# backplane.net
KiCad netlist of a schematic drawn in EAGLE
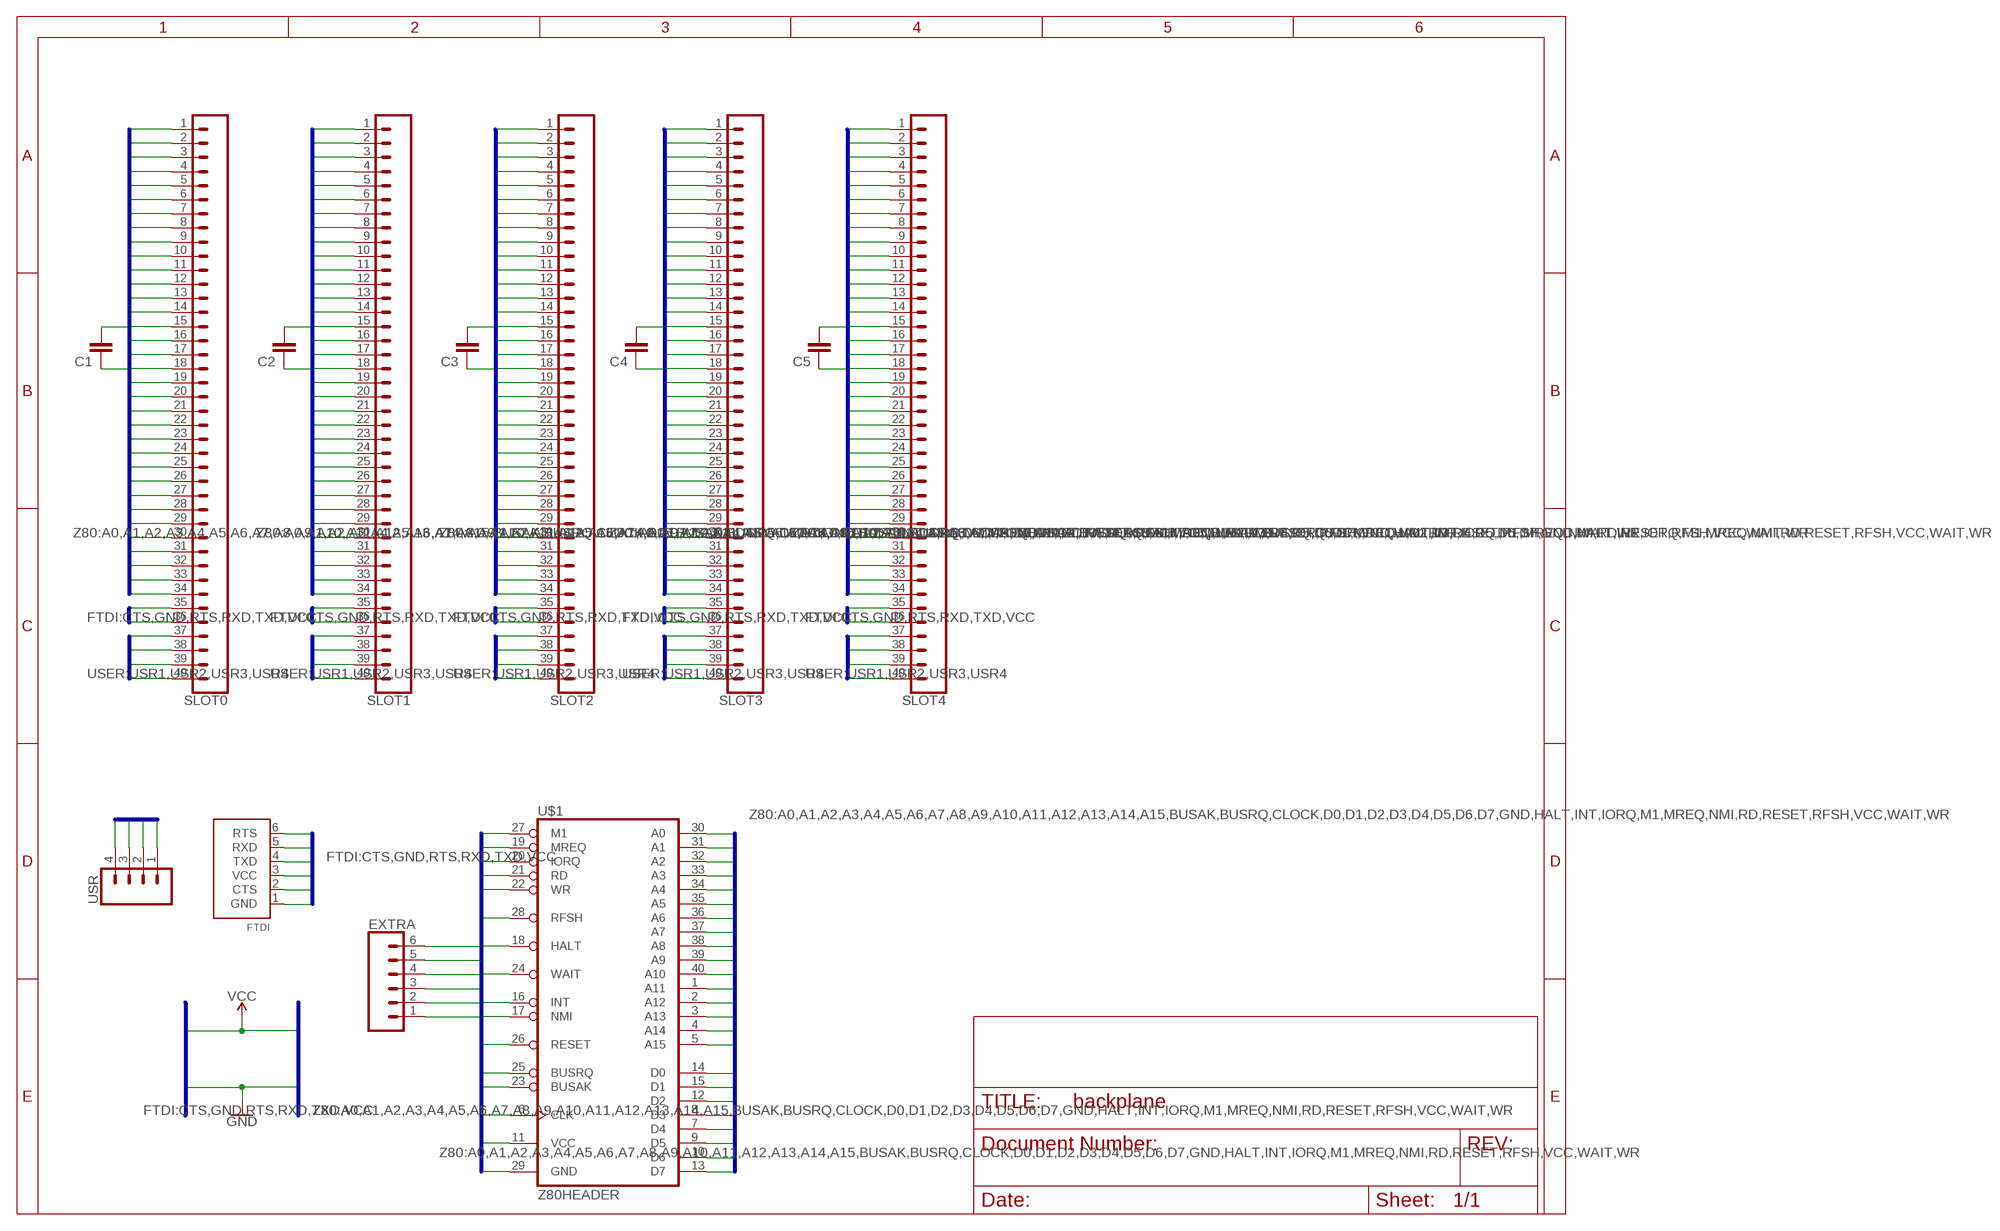
[diagram p0: schematic, sheet 1]

(export (version "E")
  (design (tool "Eeschema 10.0.6"))
  (components
    (comp (ref "C1")
      (value "C2,5-3")
      (footprint "eagle-import:C2.5-3")
      (libsource (lib "eagle-import") (part "C2,5-3"))
    )
    (comp (ref "C2")
      (value "C2,5-3")
      (footprint "eagle-import:C2.5-3")
      (libsource (lib "eagle-import") (part "C2,5-3"))
    )
    (comp (ref "C3")
      (value "C2,5-3")
      (footprint "eagle-import:C2.5-3")
      (libsource (lib "eagle-import") (part "C2,5-3"))
    )
    (comp (ref "C4")
      (value "C2,5-3")
      (footprint "eagle-import:C2.5-3")
      (libsource (lib "eagle-import") (part "C2,5-3"))
    )
    (comp (ref "C5")
      (value "C2,5-3")
      (footprint "eagle-import:C2.5-3")
      (libsource (lib "eagle-import") (part "C2,5-3"))
    )
    (comp (ref "EXTRA")
      (value "CONN_06LOCK")
      (footprint "eagle-import:1X06_LOCK")
      (libsource (lib "eagle-import") (part "CONN_06LOCK"))
    )
    (comp (ref "FTDI")
      (value "FTDIUSBCABLE")
      (footprint "eagle-import:1X06_ROUND")
      (libsource (lib "eagle-import") (part "FTDIUSBCABLE"))
    )
    (comp (ref "SLOT0")
      (value "CONN_40")
      (footprint "eagle-import:1X40")
      (libsource (lib "eagle-import") (part "CONN_40"))
    )
    (comp (ref "SLOT1")
      (value "CONN_40")
      (footprint "eagle-import:1X40")
      (libsource (lib "eagle-import") (part "CONN_40"))
    )
    (comp (ref "SLOT2")
      (value "CONN_40")
      (footprint "eagle-import:1X40")
      (libsource (lib "eagle-import") (part "CONN_40"))
    )
    (comp (ref "SLOT3")
      (value "CONN_40")
      (footprint "eagle-import:1X40")
      (libsource (lib "eagle-import") (part "CONN_40"))
    )
    (comp (ref "SLOT4")
      (value "CONN_40")
      (footprint "eagle-import:1X40")
      (libsource (lib "eagle-import") (part "CONN_40"))
    )
    (comp (ref "U$1")
      (value "Z80HEADER")
      (footprint "eagle-import:2X20")
      (libsource (lib "eagle-import") (part "Z80HEADER"))
    )
    (comp (ref "USR")
      (value "CONN_04PTH")
      (footprint "eagle-import:1X04")
      (libsource (lib "eagle-import") (part "CONN_04PTH"))
    )
  )
  (nets
    (net (code "4") (name "/A0") (class "Default")
      (node (ref "SLOT0") (pin "16") (pinfunction "16_16") (pintype "passive"))
      (node (ref "SLOT1") (pin "16") (pinfunction "16_16") (pintype "passive"))
      (node (ref "SLOT2") (pin "16") (pinfunction "16_16") (pintype "passive"))
      (node (ref "SLOT3") (pin "16") (pinfunction "16_16") (pintype "passive"))
      (node (ref "SLOT4") (pin "16") (pinfunction "16_16") (pintype "passive"))
      (node (ref "U$1") (pin "30") (pinfunction "A0_30") (pintype "output"))
    )
    (net (code "5") (name "/A1") (class "Default")
      (node (ref "SLOT0") (pin "15") (pinfunction "15_15") (pintype "passive"))
      (node (ref "SLOT1") (pin "15") (pinfunction "15_15") (pintype "passive"))
      (node (ref "SLOT2") (pin "15") (pinfunction "15_15") (pintype "passive"))
      (node (ref "SLOT3") (pin "15") (pinfunction "15_15") (pintype "passive"))
      (node (ref "SLOT4") (pin "15") (pinfunction "15_15") (pintype "passive"))
      (node (ref "U$1") (pin "31") (pinfunction "A1_31") (pintype "output"))
    )
    (net (code "6") (name "/A2") (class "Default")
      (node (ref "SLOT0") (pin "14") (pinfunction "14_14") (pintype "passive"))
      (node (ref "SLOT1") (pin "14") (pinfunction "14_14") (pintype "passive"))
      (node (ref "SLOT2") (pin "14") (pinfunction "14_14") (pintype "passive"))
      (node (ref "SLOT3") (pin "14") (pinfunction "14_14") (pintype "passive"))
      (node (ref "SLOT4") (pin "14") (pinfunction "14_14") (pintype "passive"))
      (node (ref "U$1") (pin "32") (pinfunction "A2_32") (pintype "output"))
    )
    (net (code "7") (name "/A3") (class "Default")
      (node (ref "SLOT0") (pin "13") (pinfunction "13_13") (pintype "passive"))
      (node (ref "SLOT1") (pin "13") (pinfunction "13_13") (pintype "passive"))
      (node (ref "SLOT2") (pin "13") (pinfunction "13_13") (pintype "passive"))
      (node (ref "SLOT3") (pin "13") (pinfunction "13_13") (pintype "passive"))
      (node (ref "SLOT4") (pin "13") (pinfunction "13_13") (pintype "passive"))
      (node (ref "U$1") (pin "33") (pinfunction "A3_33") (pintype "output"))
    )
    (net (code "8") (name "/A4") (class "Default")
      (node (ref "SLOT0") (pin "12") (pinfunction "12_12") (pintype "passive"))
      (node (ref "SLOT1") (pin "12") (pinfunction "12_12") (pintype "passive"))
      (node (ref "SLOT2") (pin "12") (pinfunction "12_12") (pintype "passive"))
      (node (ref "SLOT3") (pin "12") (pinfunction "12_12") (pintype "passive"))
      (node (ref "SLOT4") (pin "12") (pinfunction "12_12") (pintype "passive"))
      (node (ref "U$1") (pin "34") (pinfunction "A4_34") (pintype "output"))
    )
    (net (code "9") (name "/A5") (class "Default")
      (node (ref "SLOT0") (pin "11") (pinfunction "11_11") (pintype "passive"))
      (node (ref "SLOT1") (pin "11") (pinfunction "11_11") (pintype "passive"))
      (node (ref "SLOT2") (pin "11") (pinfunction "11_11") (pintype "passive"))
      (node (ref "SLOT3") (pin "11") (pinfunction "11_11") (pintype "passive"))
      (node (ref "SLOT4") (pin "11") (pinfunction "11_11") (pintype "passive"))
      (node (ref "U$1") (pin "35") (pinfunction "A5_35") (pintype "output"))
    )
    (net (code "10") (name "/A6") (class "Default")
      (node (ref "SLOT0") (pin "10") (pinfunction "10_10") (pintype "passive"))
      (node (ref "SLOT1") (pin "10") (pinfunction "10_10") (pintype "passive"))
      (node (ref "SLOT2") (pin "10") (pinfunction "10_10") (pintype "passive"))
      (node (ref "SLOT3") (pin "10") (pinfunction "10_10") (pintype "passive"))
      (node (ref "SLOT4") (pin "10") (pinfunction "10_10") (pintype "passive"))
      (node (ref "U$1") (pin "36") (pinfunction "A6_36") (pintype "output"))
    )
    (net (code "11") (name "/A7") (class "Default")
      (node (ref "SLOT0") (pin "9") (pinfunction "9_9") (pintype "passive"))
      (node (ref "SLOT1") (pin "9") (pinfunction "9_9") (pintype "passive"))
      (node (ref "SLOT2") (pin "9") (pinfunction "9_9") (pintype "passive"))
      (node (ref "SLOT3") (pin "9") (pinfunction "9_9") (pintype "passive"))
      (node (ref "SLOT4") (pin "9") (pinfunction "9_9") (pintype "passive"))
      (node (ref "U$1") (pin "37") (pinfunction "A7_37") (pintype "output"))
    )
    (net (code "12") (name "/A8") (class "Default")
      (node (ref "SLOT0") (pin "8") (pinfunction "8_8") (pintype "passive"))
      (node (ref "SLOT1") (pin "8") (pinfunction "8_8") (pintype "passive"))
      (node (ref "SLOT2") (pin "8") (pinfunction "8_8") (pintype "passive"))
      (node (ref "SLOT3") (pin "8") (pinfunction "8_8") (pintype "passive"))
      (node (ref "SLOT4") (pin "8") (pinfunction "8_8") (pintype "passive"))
      (node (ref "U$1") (pin "38") (pinfunction "A8_38") (pintype "output"))
    )
    (net (code "13") (name "/A9") (class "Default")
      (node (ref "SLOT0") (pin "7") (pinfunction "7_7") (pintype "passive"))
      (node (ref "SLOT1") (pin "7") (pinfunction "7_7") (pintype "passive"))
      (node (ref "SLOT2") (pin "7") (pinfunction "7_7") (pintype "passive"))
      (node (ref "SLOT3") (pin "7") (pinfunction "7_7") (pintype "passive"))
      (node (ref "SLOT4") (pin "7") (pinfunction "7_7") (pintype "passive"))
      (node (ref "U$1") (pin "39") (pinfunction "A9_39") (pintype "output"))
    )
    (net (code "14") (name "/A10") (class "Default")
      (node (ref "SLOT0") (pin "6") (pinfunction "6_6") (pintype "passive"))
      (node (ref "SLOT1") (pin "6") (pinfunction "6_6") (pintype "passive"))
      (node (ref "SLOT2") (pin "6") (pinfunction "6_6") (pintype "passive"))
      (node (ref "SLOT3") (pin "6") (pinfunction "6_6") (pintype "passive"))
      (node (ref "SLOT4") (pin "6") (pinfunction "6_6") (pintype "passive"))
      (node (ref "U$1") (pin "40") (pinfunction "A10_40") (pintype "output"))
    )
    (net (code "15") (name "/A11") (class "Default")
      (node (ref "SLOT0") (pin "5") (pinfunction "5_5") (pintype "passive"))
      (node (ref "SLOT1") (pin "5") (pinfunction "5_5") (pintype "passive"))
      (node (ref "SLOT2") (pin "5") (pinfunction "5_5") (pintype "passive"))
      (node (ref "SLOT3") (pin "5") (pinfunction "5_5") (pintype "passive"))
      (node (ref "SLOT4") (pin "5") (pinfunction "5_5") (pintype "passive"))
      (node (ref "U$1") (pin "1") (pinfunction "A11_1") (pintype "output"))
    )
    (net (code "16") (name "/A12") (class "Default")
      (node (ref "SLOT0") (pin "4") (pinfunction "4_4") (pintype "passive"))
      (node (ref "SLOT1") (pin "4") (pinfunction "4_4") (pintype "passive"))
      (node (ref "SLOT2") (pin "4") (pinfunction "4_4") (pintype "passive"))
      (node (ref "SLOT3") (pin "4") (pinfunction "4_4") (pintype "passive"))
      (node (ref "SLOT4") (pin "4") (pinfunction "4_4") (pintype "passive"))
      (node (ref "U$1") (pin "2") (pinfunction "A12_2") (pintype "output"))
    )
    (net (code "17") (name "/A13") (class "Default")
      (node (ref "SLOT0") (pin "3") (pinfunction "3_3") (pintype "passive"))
      (node (ref "SLOT1") (pin "3") (pinfunction "3_3") (pintype "passive"))
      (node (ref "SLOT2") (pin "3") (pinfunction "3_3") (pintype "passive"))
      (node (ref "SLOT3") (pin "3") (pinfunction "3_3") (pintype "passive"))
      (node (ref "SLOT4") (pin "3") (pinfunction "3_3") (pintype "passive"))
      (node (ref "U$1") (pin "3") (pinfunction "A13_3") (pintype "output"))
    )
    (net (code "18") (name "/A14") (class "Default")
      (node (ref "SLOT0") (pin "2") (pinfunction "2_2") (pintype "passive"))
      (node (ref "SLOT1") (pin "2") (pinfunction "2_2") (pintype "passive"))
      (node (ref "SLOT2") (pin "2") (pinfunction "2_2") (pintype "passive"))
      (node (ref "SLOT3") (pin "2") (pinfunction "2_2") (pintype "passive"))
      (node (ref "SLOT4") (pin "2") (pinfunction "2_2") (pintype "passive"))
      (node (ref "U$1") (pin "4") (pinfunction "A14_4") (pintype "output"))
    )
    (net (code "19") (name "/A15") (class "Default")
      (node (ref "SLOT0") (pin "1") (pinfunction "1_1") (pintype "passive"))
      (node (ref "SLOT1") (pin "1") (pinfunction "1_1") (pintype "passive"))
      (node (ref "SLOT2") (pin "1") (pinfunction "1_1") (pintype "passive"))
      (node (ref "SLOT3") (pin "1") (pinfunction "1_1") (pintype "passive"))
      (node (ref "SLOT4") (pin "1") (pinfunction "1_1") (pintype "passive"))
      (node (ref "U$1") (pin "5") (pinfunction "A15_5") (pintype "output"))
    )
    (net (code "20") (name "/BUSAK") (class "Default")
      (node (ref "EXTRA") (pin "6") (pinfunction "6_6") (pintype "passive"))
      (node (ref "U$1") (pin "23") (pinfunction "BUSAK_23") (pintype "output"))
    )
    (net (code "21") (name "/BUSRQ") (class "Default")
      (node (ref "EXTRA") (pin "5") (pinfunction "5_5") (pintype "passive"))
      (node (ref "U$1") (pin "25") (pinfunction "BUSRQ_25") (pintype "input"))
    )
    (net (code "22") (name "/CLOCK") (class "Default")
      (node (ref "SLOT0") (pin "21") (pinfunction "21_21") (pintype "passive"))
      (node (ref "SLOT1") (pin "21") (pinfunction "21_21") (pintype "passive"))
      (node (ref "SLOT2") (pin "21") (pinfunction "21_21") (pintype "passive"))
      (node (ref "SLOT3") (pin "21") (pinfunction "21_21") (pintype "passive"))
      (node (ref "SLOT4") (pin "21") (pinfunction "21_21") (pintype "passive"))
      (node (ref "U$1") (pin "6") (pinfunction "CLK_6") (pintype "input"))
    )
    (net (code "23") (name "/D0") (class "Default")
      (node (ref "SLOT0") (pin "27") (pinfunction "27_27") (pintype "passive"))
      (node (ref "SLOT1") (pin "27") (pinfunction "27_27") (pintype "passive"))
      (node (ref "SLOT2") (pin "27") (pinfunction "27_27") (pintype "passive"))
      (node (ref "SLOT3") (pin "27") (pinfunction "27_27") (pintype "passive"))
      (node (ref "SLOT4") (pin "27") (pinfunction "27_27") (pintype "passive"))
      (node (ref "U$1") (pin "14") (pinfunction "D0_14") (pintype "bidirectional"))
    )
    (net (code "24") (name "/D1") (class "Default")
      (node (ref "SLOT0") (pin "28") (pinfunction "28_28") (pintype "passive"))
      (node (ref "SLOT1") (pin "28") (pinfunction "28_28") (pintype "passive"))
      (node (ref "SLOT2") (pin "28") (pinfunction "28_28") (pintype "passive"))
      (node (ref "SLOT3") (pin "28") (pinfunction "28_28") (pintype "passive"))
      (node (ref "SLOT4") (pin "28") (pinfunction "28_28") (pintype "passive"))
      (node (ref "U$1") (pin "15") (pinfunction "D1_15") (pintype "bidirectional"))
    )
    (net (code "25") (name "/D2") (class "Default")
      (node (ref "SLOT0") (pin "29") (pinfunction "29_29") (pintype "passive"))
      (node (ref "SLOT1") (pin "29") (pinfunction "29_29") (pintype "passive"))
      (node (ref "SLOT2") (pin "29") (pinfunction "29_29") (pintype "passive"))
      (node (ref "SLOT3") (pin "29") (pinfunction "29_29") (pintype "passive"))
      (node (ref "SLOT4") (pin "29") (pinfunction "29_29") (pintype "passive"))
      (node (ref "U$1") (pin "12") (pinfunction "D2_12") (pintype "bidirectional"))
    )
    (net (code "26") (name "/D3") (class "Default")
      (node (ref "SLOT0") (pin "30") (pinfunction "30_30") (pintype "passive"))
      (node (ref "SLOT1") (pin "30") (pinfunction "30_30") (pintype "passive"))
      (node (ref "SLOT2") (pin "30") (pinfunction "30_30") (pintype "passive"))
      (node (ref "SLOT3") (pin "30") (pinfunction "30_30") (pintype "passive"))
      (node (ref "SLOT4") (pin "30") (pinfunction "30_30") (pintype "passive"))
      (node (ref "U$1") (pin "8") (pinfunction "D3_8") (pintype "bidirectional"))
    )
    (net (code "27") (name "/D4") (class "Default")
      (node (ref "SLOT0") (pin "31") (pinfunction "31_31") (pintype "passive"))
      (node (ref "SLOT1") (pin "31") (pinfunction "31_31") (pintype "passive"))
      (node (ref "SLOT2") (pin "31") (pinfunction "31_31") (pintype "passive"))
      (node (ref "SLOT3") (pin "31") (pinfunction "31_31") (pintype "passive"))
      (node (ref "SLOT4") (pin "31") (pinfunction "31_31") (pintype "passive"))
      (node (ref "U$1") (pin "7") (pinfunction "D4_7") (pintype "bidirectional"))
    )
    (net (code "28") (name "/D5") (class "Default")
      (node (ref "SLOT0") (pin "32") (pinfunction "32_32") (pintype "passive"))
      (node (ref "SLOT1") (pin "32") (pinfunction "32_32") (pintype "passive"))
      (node (ref "SLOT2") (pin "32") (pinfunction "32_32") (pintype "passive"))
      (node (ref "SLOT3") (pin "32") (pinfunction "32_32") (pintype "passive"))
      (node (ref "SLOT4") (pin "32") (pinfunction "32_32") (pintype "passive"))
      (node (ref "U$1") (pin "9") (pinfunction "D5_9") (pintype "bidirectional"))
    )
    (net (code "29") (name "/D6") (class "Default")
      (node (ref "SLOT0") (pin "33") (pinfunction "33_33") (pintype "passive"))
      (node (ref "SLOT1") (pin "33") (pinfunction "33_33") (pintype "passive"))
      (node (ref "SLOT2") (pin "33") (pinfunction "33_33") (pintype "passive"))
      (node (ref "SLOT3") (pin "33") (pinfunction "33_33") (pintype "passive"))
      (node (ref "SLOT4") (pin "33") (pinfunction "33_33") (pintype "passive"))
      (node (ref "U$1") (pin "10") (pinfunction "D6_10") (pintype "bidirectional"))
    )
    (net (code "30") (name "/D7") (class "Default")
      (node (ref "SLOT0") (pin "34") (pinfunction "34_34") (pintype "passive"))
      (node (ref "SLOT1") (pin "34") (pinfunction "34_34") (pintype "passive"))
      (node (ref "SLOT2") (pin "34") (pinfunction "34_34") (pintype "passive"))
      (node (ref "SLOT3") (pin "34") (pinfunction "34_34") (pintype "passive"))
      (node (ref "SLOT4") (pin "34") (pinfunction "34_34") (pintype "passive"))
      (node (ref "U$1") (pin "13") (pinfunction "D7_13") (pintype "bidirectional"))
    )
    (net (code "31") (name "/FTDI:CTS") (class "Default")
      (node (ref "FTDI") (pin "5") (pinfunction "RXD_5") (pintype "bidirectional"))
      (node (ref "SLOT0") (pin "36") (pinfunction "36_36") (pintype "passive"))
      (node (ref "SLOT1") (pin "36") (pinfunction "36_36") (pintype "passive"))
      (node (ref "SLOT2") (pin "36") (pinfunction "36_36") (pintype "passive"))
      (node (ref "SLOT3") (pin "36") (pinfunction "36_36") (pintype "passive"))
      (node (ref "SLOT4") (pin "36") (pinfunction "36_36") (pintype "passive"))
    )
    (net (code "32") (name "/HALT") (class "Default")
      (node (ref "EXTRA") (pin "3") (pinfunction "3_3") (pintype "passive"))
      (node (ref "U$1") (pin "18") (pinfunction "HALT_18") (pintype "output"))
    )
    (net (code "33") (name "/INT") (class "Default")
      (node (ref "SLOT0") (pin "22") (pinfunction "22_22") (pintype "passive"))
      (node (ref "SLOT1") (pin "22") (pinfunction "22_22") (pintype "passive"))
      (node (ref "SLOT2") (pin "22") (pinfunction "22_22") (pintype "passive"))
      (node (ref "SLOT3") (pin "22") (pinfunction "22_22") (pintype "passive"))
      (node (ref "SLOT4") (pin "22") (pinfunction "22_22") (pintype "passive"))
      (node (ref "U$1") (pin "16") (pinfunction "INT_16") (pintype "input"))
    )
    (net (code "34") (name "/IORQ") (class "Default")
      (node (ref "SLOT0") (pin "26") (pinfunction "26_26") (pintype "passive"))
      (node (ref "SLOT1") (pin "26") (pinfunction "26_26") (pintype "passive"))
      (node (ref "SLOT2") (pin "26") (pinfunction "26_26") (pintype "passive"))
      (node (ref "SLOT3") (pin "26") (pinfunction "26_26") (pintype "passive"))
      (node (ref "SLOT4") (pin "26") (pinfunction "26_26") (pintype "passive"))
      (node (ref "U$1") (pin "20") (pinfunction "IORQ_20") (pintype "output"))
    )
    (net (code "35") (name "/M1") (class "Default")
      (node (ref "SLOT0") (pin "19") (pinfunction "19_19") (pintype "passive"))
      (node (ref "SLOT1") (pin "19") (pinfunction "19_19") (pintype "passive"))
      (node (ref "SLOT2") (pin "19") (pinfunction "19_19") (pintype "passive"))
      (node (ref "SLOT3") (pin "19") (pinfunction "19_19") (pintype "passive"))
      (node (ref "SLOT4") (pin "19") (pinfunction "19_19") (pintype "passive"))
      (node (ref "U$1") (pin "27") (pinfunction "M1_27") (pintype "output"))
    )
    (net (code "36") (name "/MREQ") (class "Default")
      (node (ref "SLOT0") (pin "23") (pinfunction "23_23") (pintype "passive"))
      (node (ref "SLOT1") (pin "23") (pinfunction "23_23") (pintype "passive"))
      (node (ref "SLOT2") (pin "23") (pinfunction "23_23") (pintype "passive"))
      (node (ref "SLOT3") (pin "23") (pinfunction "23_23") (pintype "passive"))
      (node (ref "SLOT4") (pin "23") (pinfunction "23_23") (pintype "passive"))
      (node (ref "U$1") (pin "19") (pinfunction "MREQ_19") (pintype "output"))
    )
    (net (code "37") (name "/NMI") (class "Default")
      (node (ref "EXTRA") (pin "2") (pinfunction "2_2") (pintype "passive"))
      (node (ref "U$1") (pin "17") (pinfunction "NMI_17") (pintype "input"))
    )
    (net (code "38") (name "/RD") (class "Default")
      (node (ref "SLOT0") (pin "25") (pinfunction "25_25") (pintype "passive"))
      (node (ref "SLOT1") (pin "25") (pinfunction "25_25") (pintype "passive"))
      (node (ref "SLOT2") (pin "25") (pinfunction "25_25") (pintype "passive"))
      (node (ref "SLOT3") (pin "25") (pinfunction "25_25") (pintype "passive"))
      (node (ref "SLOT4") (pin "25") (pinfunction "25_25") (pintype "passive"))
      (node (ref "U$1") (pin "21") (pinfunction "RD_21") (pintype "output"))
    )
    (net (code "39") (name "/RESET") (class "Default")
      (node (ref "SLOT0") (pin "20") (pinfunction "20_20") (pintype "passive"))
      (node (ref "SLOT1") (pin "20") (pinfunction "20_20") (pintype "passive"))
      (node (ref "SLOT2") (pin "20") (pinfunction "20_20") (pintype "passive"))
      (node (ref "SLOT3") (pin "20") (pinfunction "20_20") (pintype "passive"))
      (node (ref "SLOT4") (pin "20") (pinfunction "20_20") (pintype "passive"))
      (node (ref "U$1") (pin "26") (pinfunction "RESET_26") (pintype "input"))
    )
    (net (code "40") (name "/RFSH") (class "Default")
      (node (ref "EXTRA") (pin "1") (pinfunction "1_1") (pintype "passive"))
      (node (ref "U$1") (pin "28") (pinfunction "RFSH_28") (pintype "output"))
    )
    (net (code "41") (name "/TXD") (class "Default")
      (node (ref "FTDI") (pin "4") (pinfunction "TXD_4") (pintype "bidirectional"))
      (node (ref "SLOT0") (pin "35") (pinfunction "35_35") (pintype "passive"))
      (node (ref "SLOT1") (pin "35") (pinfunction "35_35") (pintype "passive"))
      (node (ref "SLOT2") (pin "35") (pinfunction "35_35") (pintype "passive"))
      (node (ref "SLOT3") (pin "35") (pinfunction "35_35") (pintype "passive"))
      (node (ref "SLOT4") (pin "35") (pinfunction "35_35") (pintype "passive"))
    )
    (net (code "42") (name "/USR1") (class "Default")
      (node (ref "SLOT0") (pin "37") (pinfunction "37_37") (pintype "passive"))
      (node (ref "SLOT1") (pin "37") (pinfunction "37_37") (pintype "passive"))
      (node (ref "SLOT2") (pin "37") (pinfunction "37_37") (pintype "passive"))
      (node (ref "SLOT3") (pin "37") (pinfunction "37_37") (pintype "passive"))
      (node (ref "SLOT4") (pin "37") (pinfunction "37_37") (pintype "passive"))
      (node (ref "USR") (pin "1") (pinfunction "1_1") (pintype "passive"))
    )
    (net (code "43") (name "/USR2") (class "Default")
      (node (ref "SLOT0") (pin "38") (pinfunction "38_38") (pintype "passive"))
      (node (ref "SLOT1") (pin "38") (pinfunction "38_38") (pintype "passive"))
      (node (ref "SLOT2") (pin "38") (pinfunction "38_38") (pintype "passive"))
      (node (ref "SLOT3") (pin "38") (pinfunction "38_38") (pintype "passive"))
      (node (ref "SLOT4") (pin "38") (pinfunction "38_38") (pintype "passive"))
      (node (ref "USR") (pin "2") (pinfunction "2_2") (pintype "passive"))
    )
    (net (code "44") (name "/USR3") (class "Default")
      (node (ref "SLOT0") (pin "39") (pinfunction "39_39") (pintype "passive"))
      (node (ref "SLOT1") (pin "39") (pinfunction "39_39") (pintype "passive"))
      (node (ref "SLOT2") (pin "39") (pinfunction "39_39") (pintype "passive"))
      (node (ref "SLOT3") (pin "39") (pinfunction "39_39") (pintype "passive"))
      (node (ref "SLOT4") (pin "39") (pinfunction "39_39") (pintype "passive"))
      (node (ref "USR") (pin "3") (pinfunction "3_3") (pintype "passive"))
    )
    (net (code "45") (name "/USR4") (class "Default")
      (node (ref "SLOT0") (pin "40") (pinfunction "40_40") (pintype "passive"))
      (node (ref "SLOT1") (pin "40") (pinfunction "40_40") (pintype "passive"))
      (node (ref "SLOT2") (pin "40") (pinfunction "40_40") (pintype "passive"))
      (node (ref "SLOT3") (pin "40") (pinfunction "40_40") (pintype "passive"))
      (node (ref "SLOT4") (pin "40") (pinfunction "40_40") (pintype "passive"))
      (node (ref "USR") (pin "4") (pinfunction "4_4") (pintype "passive"))
    )
    (net (code "46") (name "/WAIT") (class "Default")
      (node (ref "EXTRA") (pin "4") (pinfunction "4_4") (pintype "passive"))
      (node (ref "U$1") (pin "24") (pinfunction "WAIT_24") (pintype "input"))
    )
    (net (code "47") (name "/WR") (class "Default")
      (node (ref "SLOT0") (pin "24") (pinfunction "24_24") (pintype "passive"))
      (node (ref "SLOT1") (pin "24") (pinfunction "24_24") (pintype "passive"))
      (node (ref "SLOT2") (pin "24") (pinfunction "24_24") (pintype "passive"))
      (node (ref "SLOT3") (pin "24") (pinfunction "24_24") (pintype "passive"))
      (node (ref "SLOT4") (pin "24") (pinfunction "24_24") (pintype "passive"))
      (node (ref "U$1") (pin "22") (pinfunction "WR_22") (pintype "output"))
    )
    (net (code "50") (name "GND") (class "Default")
      (node (ref "C1") (pin "1") (pinfunction "1_1") (pintype "passive"))
      (node (ref "C2") (pin "1") (pinfunction "1_1") (pintype "passive"))
      (node (ref "C3") (pin "1") (pinfunction "1_1") (pintype "passive"))
      (node (ref "C4") (pin "1") (pinfunction "1_1") (pintype "passive"))
      (node (ref "C5") (pin "1") (pinfunction "1_1") (pintype "passive"))
      (node (ref "FTDI") (pin "1") (pinfunction "GND_1") (pintype "bidirectional"))
      (node (ref "SLOT0") (pin "17") (pinfunction "17_17") (pintype "passive"))
      (node (ref "SLOT1") (pin "17") (pinfunction "17_17") (pintype "passive"))
      (node (ref "SLOT2") (pin "17") (pinfunction "17_17") (pintype "passive"))
      (node (ref "SLOT3") (pin "17") (pinfunction "17_17") (pintype "passive"))
      (node (ref "SLOT4") (pin "17") (pinfunction "17_17") (pintype "passive"))
      (node (ref "U$1") (pin "29") (pinfunction "GND_29") (pintype "power_in"))
    )
    (net (code "51") (name "VCC") (class "Default")
      (node (ref "C1") (pin "2") (pinfunction "2_2") (pintype "passive"))
      (node (ref "C2") (pin "2") (pinfunction "2_2") (pintype "passive"))
      (node (ref "C3") (pin "2") (pinfunction "2_2") (pintype "passive"))
      (node (ref "C4") (pin "2") (pinfunction "2_2") (pintype "passive"))
      (node (ref "C5") (pin "2") (pinfunction "2_2") (pintype "passive"))
      (node (ref "FTDI") (pin "3") (pinfunction "VCC_3") (pintype "bidirectional"))
      (node (ref "SLOT0") (pin "18") (pinfunction "18_18") (pintype "passive"))
      (node (ref "SLOT1") (pin "18") (pinfunction "18_18") (pintype "passive"))
      (node (ref "SLOT2") (pin "18") (pinfunction "18_18") (pintype "passive"))
      (node (ref "SLOT3") (pin "18") (pinfunction "18_18") (pintype "passive"))
      (node (ref "SLOT4") (pin "18") (pinfunction "18_18") (pintype "passive"))
      (node (ref "U$1") (pin "11") (pinfunction "VCC_11") (pintype "power_in"))
    )
    (net (code "52") (name "unconnected-(FTDI-CTS-Pad2)") (class "Default")
      (node (ref "FTDI") (pin "2") (pinfunction "CTS_2") (pintype "bidirectional"))
    )
    (net (code "53") (name "unconnected-(FTDI-RTS-Pad6)") (class "Default")
      (node (ref "FTDI") (pin "6") (pinfunction "RTS_6") (pintype "bidirectional"))
    )
  )
)
